# GSRv2.net
KiCad netlist of a schematic drawn in EAGLE
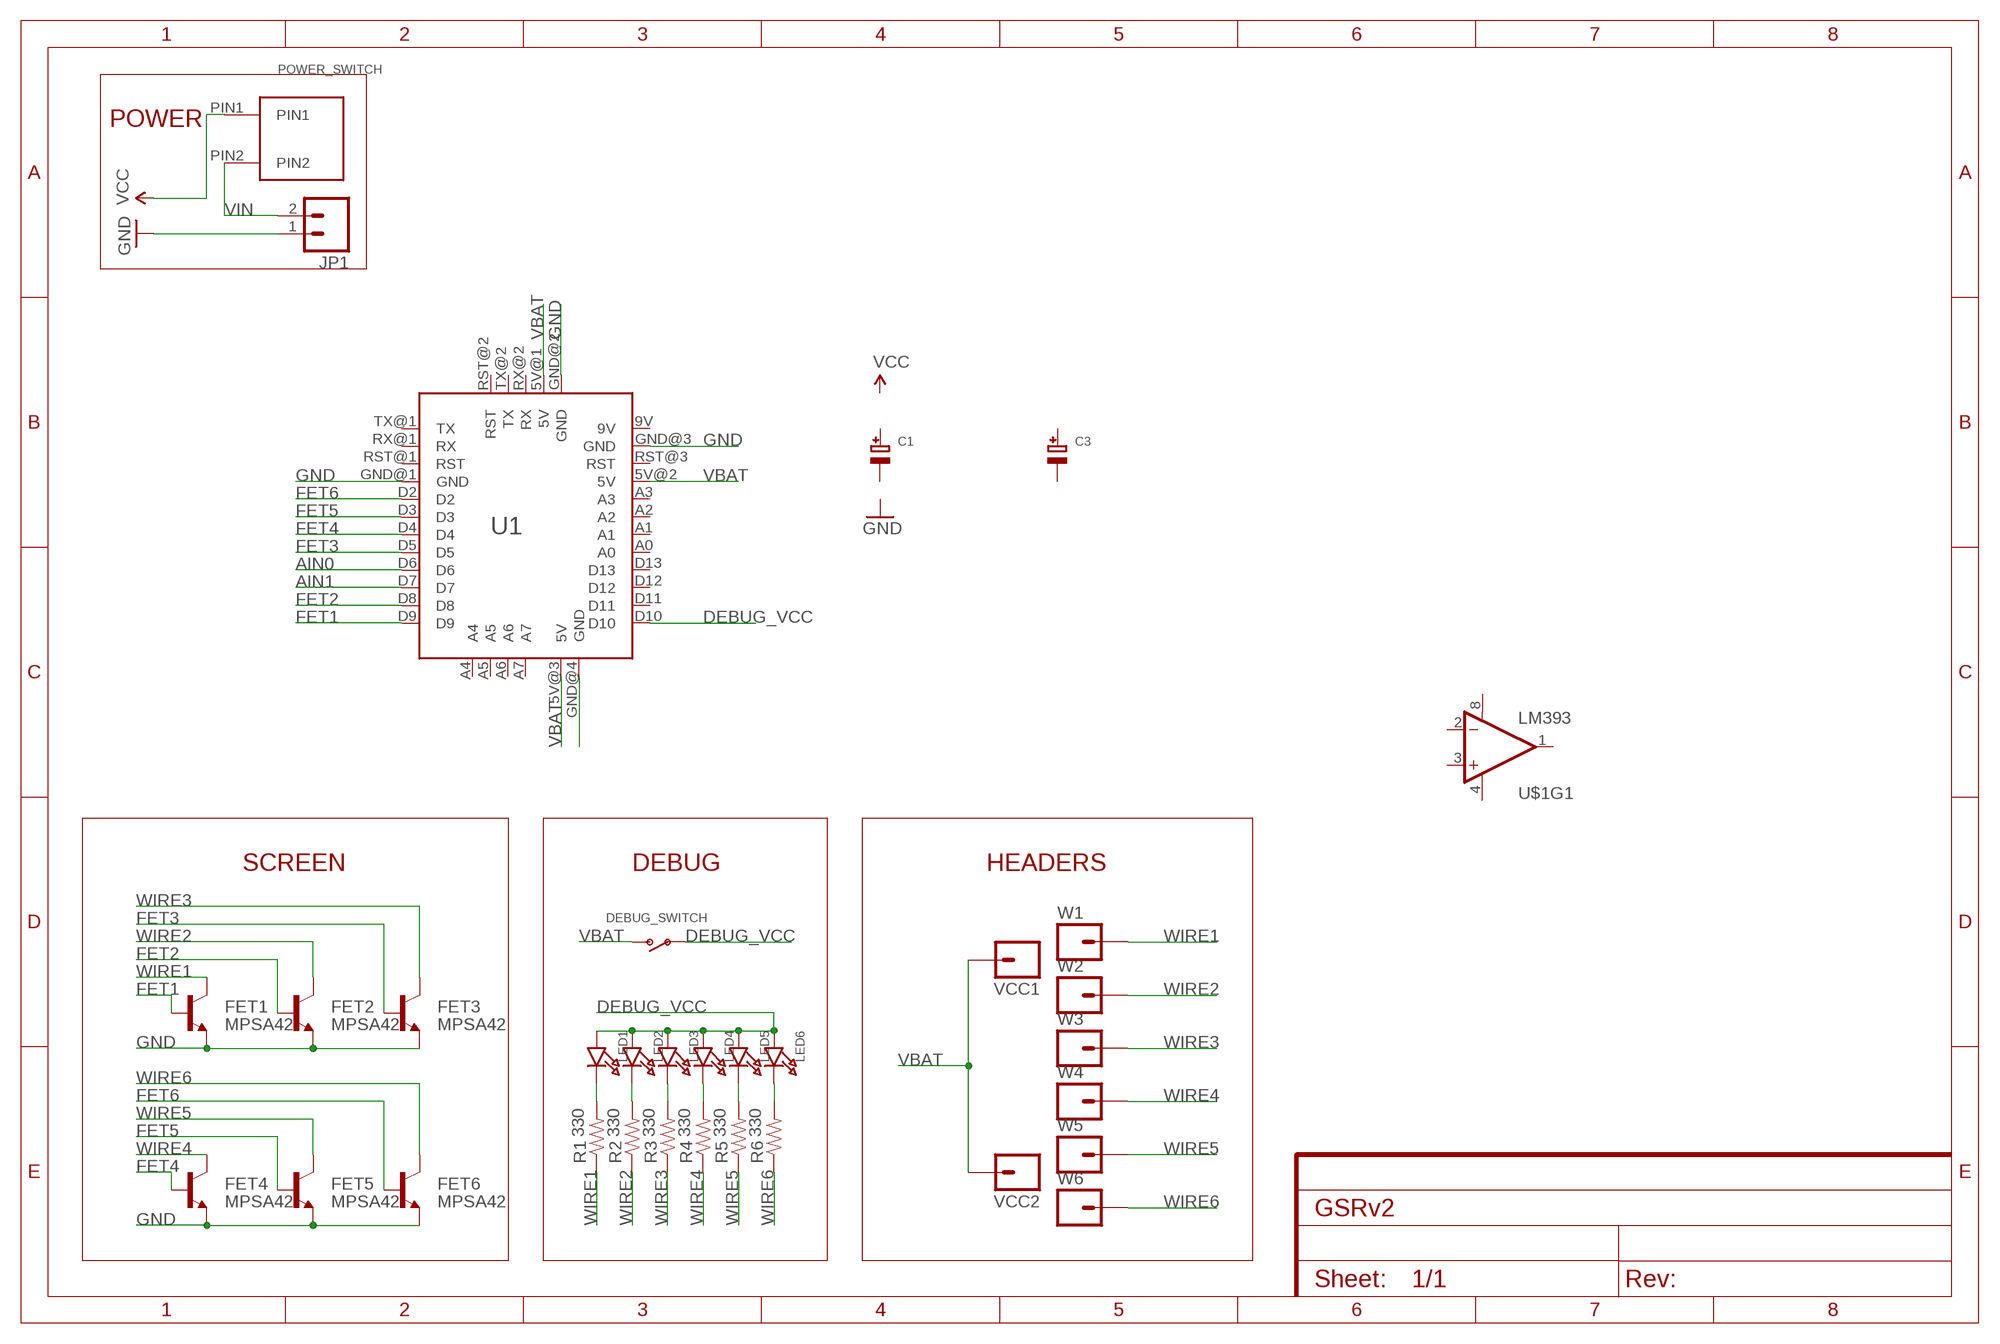
[diagram p0: schematic, sheet 1]

(export (version "E")
  (design (tool "Eeschema 10.0.6"))
  (components
    (comp (ref "C1")
      (value "CAP_TANTALUMB/3528_WAVE")
      (footprint "eagle-import:EIA3528-21_B-W")
      (libsource (lib "eagle-import") (part "CAP_TANTALUMB/3528_WAVE"))
    )
    (comp (ref "C3")
      (value "CAP_TANTALUMB/3528_WAVE")
      (footprint "eagle-import:EIA3528-21_B-W")
      (libsource (lib "eagle-import") (part "CAP_TANTALUMB/3528_WAVE"))
    )
    (comp (ref "DEBUG_SWITCH")
      (value "SWITCH_SPST")
      (footprint "eagle-import:SPST_SMT_19192")
      (libsource (lib "eagle-import") (part "SWITCH_SPST"))
    )
    (comp (ref "FET1")
      (value "MPSA42")
      (footprint "eagle-import:SOT23-3")
      (libsource (lib "eagle-import") (part "TRANSISTOR_NPNMPSA42"))
    )
    (comp (ref "FET2")
      (value "MPSA42")
      (footprint "eagle-import:SOT23-3")
      (libsource (lib "eagle-import") (part "TRANSISTOR_NPNMPSA42"))
    )
    (comp (ref "FET3")
      (value "MPSA42")
      (footprint "eagle-import:SOT23-3")
      (libsource (lib "eagle-import") (part "TRANSISTOR_NPNMPSA42"))
    )
    (comp (ref "FET4")
      (value "MPSA42")
      (footprint "eagle-import:SOT23-3")
      (libsource (lib "eagle-import") (part "TRANSISTOR_NPNMPSA42"))
    )
    (comp (ref "FET5")
      (value "MPSA42")
      (footprint "eagle-import:SOT23-3")
      (libsource (lib "eagle-import") (part "TRANSISTOR_NPNMPSA42"))
    )
    (comp (ref "FET6")
      (value "MPSA42")
      (footprint "eagle-import:SOT23-3")
      (libsource (lib "eagle-import") (part "TRANSISTOR_NPNMPSA42"))
    )
    (comp (ref "JP1")
      (value "M02-JST-2MM-SMT")
      (footprint "eagle-import:JST-2-SMD")
      (libsource (lib "eagle-import") (part "M02-JST-2MM-SMT"))
    )
    (comp (ref "LED1")
      (value "LED0603_NOOUTLINE")
      (footprint "eagle-import:CHIPLED_0603_NOOUTLINE")
      (libsource (lib "eagle-import") (part "LED0603_NOOUTLINE"))
    )
    (comp (ref "LED2")
      (value "LED0603_NOOUTLINE")
      (footprint "eagle-import:CHIPLED_0603_NOOUTLINE")
      (libsource (lib "eagle-import") (part "LED0603_NOOUTLINE"))
    )
    (comp (ref "LED3")
      (value "LED0603_NOOUTLINE")
      (footprint "eagle-import:CHIPLED_0603_NOOUTLINE")
      (libsource (lib "eagle-import") (part "LED0603_NOOUTLINE"))
    )
    (comp (ref "LED4")
      (value "LED0603_NOOUTLINE")
      (footprint "eagle-import:CHIPLED_0603_NOOUTLINE")
      (libsource (lib "eagle-import") (part "LED0603_NOOUTLINE"))
    )
    (comp (ref "LED5")
      (value "LED0603_NOOUTLINE")
      (footprint "eagle-import:CHIPLED_0603_NOOUTLINE")
      (libsource (lib "eagle-import") (part "LED0603_NOOUTLINE"))
    )
    (comp (ref "LED6")
      (value "LED0603_NOOUTLINE")
      (footprint "eagle-import:CHIPLED_0603_NOOUTLINE")
      (libsource (lib "eagle-import") (part "LED0603_NOOUTLINE"))
    )
    (comp (ref "POWER_SWITCH")
      (value "PUSH_BUTTON")
      (footprint "eagle-import:PUSH_BUTTON")
      (libsource (lib "eagle-import") (part "PUSH_BUTTON"))
    )
    (comp (ref "R1")
      (value "330")
      (footprint "eagle-import:0603-RES")
      (libsource (lib "eagle-import") (part "RESISTOR0603-RES"))
    )
    (comp (ref "R2")
      (value "330")
      (footprint "eagle-import:0603-RES")
      (libsource (lib "eagle-import") (part "RESISTOR0603-RES"))
    )
    (comp (ref "R3")
      (value "330")
      (footprint "eagle-import:0603-RES")
      (libsource (lib "eagle-import") (part "RESISTOR0603-RES"))
    )
    (comp (ref "R4")
      (value "330")
      (footprint "eagle-import:0603-RES")
      (libsource (lib "eagle-import") (part "RESISTOR0603-RES"))
    )
    (comp (ref "R5")
      (value "330")
      (footprint "eagle-import:0603-RES")
      (libsource (lib "eagle-import") (part "RESISTOR0603-RES"))
    )
    (comp (ref "R6")
      (value "330")
      (footprint "eagle-import:0603-RES")
      (libsource (lib "eagle-import") (part "RESISTOR0603-RES"))
    )
    (comp (ref "U$1")
      (value "LM393")
      (footprint "eagle-import:SO08")
      (libsource (lib "eagle-import") (part "LM393"))
    )
    (comp (ref "U1")
      (value "ARDUINO_MINI")
      (footprint "eagle-import:ARDUINO_MINI")
      (libsource (lib "eagle-import") (part "ARDUINO_MINI"))
    )
    (comp (ref "VCC1")
      (value "M01NOSILK-KIT")
      (footprint "eagle-import:1X01NS-KIT")
      (libsource (lib "eagle-import") (part "M01NOSILK-KIT"))
    )
    (comp (ref "VCC2")
      (value "M01NOSILK-KIT")
      (footprint "eagle-import:1X01NS-KIT")
      (libsource (lib "eagle-import") (part "M01NOSILK-KIT"))
    )
    (comp (ref "W1")
      (value "M01NOSILK-KIT")
      (footprint "eagle-import:1X01NS-KIT")
      (libsource (lib "eagle-import") (part "M01NOSILK-KIT"))
    )
    (comp (ref "W2")
      (value "M01NOSILK-KIT")
      (footprint "eagle-import:1X01NS-KIT")
      (libsource (lib "eagle-import") (part "M01NOSILK-KIT"))
    )
    (comp (ref "W3")
      (value "M01NOSILK-KIT")
      (footprint "eagle-import:1X01NS-KIT")
      (libsource (lib "eagle-import") (part "M01NOSILK-KIT"))
    )
    (comp (ref "W4")
      (value "M01NOSILK-KIT")
      (footprint "eagle-import:1X01NS-KIT")
      (libsource (lib "eagle-import") (part "M01NOSILK-KIT"))
    )
    (comp (ref "W5")
      (value "M01NOSILK-KIT")
      (footprint "eagle-import:1X01NS-KIT")
      (libsource (lib "eagle-import") (part "M01NOSILK-KIT"))
    )
    (comp (ref "W6")
      (value "M01NOSILK-KIT")
      (footprint "eagle-import:1X01NS-KIT")
      (libsource (lib "eagle-import") (part "M01NOSILK-KIT"))
    )
  )
  (nets
    (net (code "1") (name "/9V") (class "Default")
      (node (ref "U1") (pin "9V") (pinfunction "9V_9V") (pintype "power_in"))
    )
    (net (code "2") (name "/AIN0") (class "Default")
      (node (ref "U1") (pin "D6") (pinfunction "D6_D6") (pintype "bidirectional"))
    )
    (net (code "3") (name "/AIN1") (class "Default")
      (node (ref "U1") (pin "D7") (pinfunction "D7_D7") (pintype "bidirectional"))
    )
    (net (code "4") (name "/DEBUG_VCC") (class "Default")
      (node (ref "DEBUG_SWITCH") (pin "B") (pinfunction "P_B") (pintype "passive"))
      (node (ref "LED1") (pin "A") (pinfunction "A_A") (pintype "passive"))
      (node (ref "LED2") (pin "A") (pinfunction "A_A") (pintype "passive"))
      (node (ref "LED3") (pin "A") (pinfunction "A_A") (pintype "passive"))
      (node (ref "LED4") (pin "A") (pinfunction "A_A") (pintype "passive"))
      (node (ref "LED5") (pin "A") (pinfunction "A_A") (pintype "passive"))
      (node (ref "LED6") (pin "A") (pinfunction "A_A") (pintype "passive"))
      (node (ref "U1") (pin "D10") (pinfunction "D10_D10") (pintype "bidirectional"))
    )
    (net (code "5") (name "/FET1") (class "Default")
      (node (ref "FET1") (pin "1") (pinfunction "B_1") (pintype "passive"))
      (node (ref "U1") (pin "D9") (pinfunction "D9_D9") (pintype "bidirectional"))
    )
    (net (code "6") (name "/FET2") (class "Default")
      (node (ref "FET2") (pin "1") (pinfunction "B_1") (pintype "passive"))
      (node (ref "U1") (pin "D8") (pinfunction "D8_D8") (pintype "bidirectional"))
    )
    (net (code "7") (name "/FET3") (class "Default")
      (node (ref "FET3") (pin "1") (pinfunction "B_1") (pintype "passive"))
      (node (ref "U1") (pin "D5") (pinfunction "D5_D5") (pintype "bidirectional"))
    )
    (net (code "8") (name "/FET4") (class "Default")
      (node (ref "FET4") (pin "1") (pinfunction "B_1") (pintype "passive"))
      (node (ref "U1") (pin "D4") (pinfunction "D4_D4") (pintype "bidirectional"))
    )
    (net (code "9") (name "/FET5") (class "Default")
      (node (ref "FET5") (pin "1") (pinfunction "B_1") (pintype "passive"))
      (node (ref "U1") (pin "D3") (pinfunction "D3_D3") (pintype "bidirectional"))
    )
    (net (code "10") (name "/FET6") (class "Default")
      (node (ref "FET6") (pin "1") (pinfunction "B_1") (pintype "passive"))
      (node (ref "U1") (pin "D2") (pinfunction "D2_D2") (pintype "bidirectional"))
    )
    (net (code "11") (name "/V+") (class "Default")
      (node (ref "U$1") (pin "8") (pinfunction "V+_8") (pintype "power_in"))
    )
    (net (code "12") (name "/V-") (class "Default")
      (node (ref "U$1") (pin "4") (pinfunction "V-_4") (pintype "power_in"))
    )
    (net (code "13") (name "/VBAT") (class "Default")
      (node (ref "DEBUG_SWITCH") (pin "C") (pinfunction "S_C") (pintype "passive"))
      (node (ref "U1") (pin "5V@1") (pinfunction "5V_5V@1") (pintype "power_in"))
      (node (ref "U1") (pin "5V@2") (pinfunction "5V_5V@2") (pintype "power_in"))
      (node (ref "U1") (pin "5V@3") (pinfunction "5V_5V@3") (pintype "power_in"))
      (node (ref "VCC1") (pin "1") (pinfunction "1_1") (pintype "passive"))
      (node (ref "VCC2") (pin "1") (pinfunction "1_1") (pintype "passive"))
    )
    (net (code "14") (name "/VIN") (class "Default")
      (node (ref "JP1") (pin "2") (pinfunction "1_2") (pintype "passive"))
      (node (ref "POWER_SWITCH") (pin "PIN2") (pinfunction "PIN2_PIN2") (pintype "bidirectional"))
    )
    (net (code "15") (name "/WIRE1") (class "Default")
      (node (ref "FET1") (pin "3") (pinfunction "C_3") (pintype "passive"))
      (node (ref "R1") (pin "1") (pinfunction "1_1") (pintype "passive"))
      (node (ref "W1") (pin "1") (pinfunction "1_1") (pintype "passive"))
    )
    (net (code "16") (name "/WIRE2") (class "Default")
      (node (ref "FET2") (pin "3") (pinfunction "C_3") (pintype "passive"))
      (node (ref "R2") (pin "1") (pinfunction "1_1") (pintype "passive"))
      (node (ref "W2") (pin "1") (pinfunction "1_1") (pintype "passive"))
    )
    (net (code "17") (name "/WIRE3") (class "Default")
      (node (ref "FET3") (pin "3") (pinfunction "C_3") (pintype "passive"))
      (node (ref "R3") (pin "1") (pinfunction "1_1") (pintype "passive"))
      (node (ref "W3") (pin "1") (pinfunction "1_1") (pintype "passive"))
    )
    (net (code "18") (name "/WIRE4") (class "Default")
      (node (ref "FET4") (pin "3") (pinfunction "C_3") (pintype "passive"))
      (node (ref "R4") (pin "1") (pinfunction "1_1") (pintype "passive"))
      (node (ref "W4") (pin "1") (pinfunction "1_1") (pintype "passive"))
    )
    (net (code "19") (name "/WIRE5") (class "Default")
      (node (ref "FET5") (pin "3") (pinfunction "C_3") (pintype "passive"))
      (node (ref "R5") (pin "1") (pinfunction "1_1") (pintype "passive"))
      (node (ref "W5") (pin "1") (pinfunction "1_1") (pintype "passive"))
    )
    (net (code "20") (name "/WIRE6") (class "Default")
      (node (ref "FET6") (pin "3") (pinfunction "C_3") (pintype "passive"))
      (node (ref "R6") (pin "1") (pinfunction "1_1") (pintype "passive"))
      (node (ref "W6") (pin "1") (pinfunction "1_1") (pintype "passive"))
    )
    (net (code "21") (name "GND") (class "Default")
      (node (ref "FET1") (pin "2") (pinfunction "E_2") (pintype "passive"))
      (node (ref "FET2") (pin "2") (pinfunction "E_2") (pintype "passive"))
      (node (ref "FET3") (pin "2") (pinfunction "E_2") (pintype "passive"))
      (node (ref "FET4") (pin "2") (pinfunction "E_2") (pintype "passive"))
      (node (ref "FET5") (pin "2") (pinfunction "E_2") (pintype "passive"))
      (node (ref "FET6") (pin "2") (pinfunction "E_2") (pintype "passive"))
      (node (ref "JP1") (pin "1") (pinfunction "2_1") (pintype "passive"))
      (node (ref "U1") (pin "GND@1") (pinfunction "GND_GND@1") (pintype "power_in"))
      (node (ref "U1") (pin "GND@2") (pinfunction "GND_GND@2") (pintype "power_in"))
      (node (ref "U1") (pin "GND@3") (pinfunction "GND_GND@3") (pintype "power_in"))
      (node (ref "U1") (pin "GND@4") (pinfunction "GND_GND@4") (pintype "power_in"))
    )
    (net (code "22") (name "Net-(LED1-PadC)") (class "Default")
      (node (ref "LED1") (pin "C") (pinfunction "C_C") (pintype "passive"))
      (node (ref "R1") (pin "2") (pinfunction "2_2") (pintype "passive"))
    )
    (net (code "23") (name "Net-(LED2-PadC)") (class "Default")
      (node (ref "LED2") (pin "C") (pinfunction "C_C") (pintype "passive"))
      (node (ref "R2") (pin "2") (pinfunction "2_2") (pintype "passive"))
    )
    (net (code "24") (name "Net-(LED3-PadC)") (class "Default")
      (node (ref "LED3") (pin "C") (pinfunction "C_C") (pintype "passive"))
      (node (ref "R3") (pin "2") (pinfunction "2_2") (pintype "passive"))
    )
    (net (code "25") (name "Net-(LED4-PadC)") (class "Default")
      (node (ref "LED4") (pin "C") (pinfunction "C_C") (pintype "passive"))
      (node (ref "R4") (pin "2") (pinfunction "2_2") (pintype "passive"))
    )
    (net (code "26") (name "Net-(LED5-PadC)") (class "Default")
      (node (ref "LED5") (pin "C") (pinfunction "C_C") (pintype "passive"))
      (node (ref "R5") (pin "2") (pinfunction "2_2") (pintype "passive"))
    )
    (net (code "27") (name "Net-(LED6-PadC)") (class "Default")
      (node (ref "LED6") (pin "C") (pinfunction "C_C") (pintype "passive"))
      (node (ref "R6") (pin "2") (pinfunction "2_2") (pintype "passive"))
    )
    (net (code "28") (name "VCC") (class "Default")
      (node (ref "POWER_SWITCH") (pin "PIN1") (pinfunction "PIN1_PIN1") (pintype "bidirectional"))
    )
    (net (code "29") (name "unconnected-(C1-Pad+)") (class "Default")
      (node (ref "C1") (pin "+") (pinfunction "+_+") (pintype "passive"))
    )
    (net (code "30") (name "unconnected-(C1-Pad-)") (class "Default")
      (node (ref "C1") (pin "-") (pinfunction "-_-") (pintype "passive"))
    )
    (net (code "31") (name "unconnected-(C3-Pad+)") (class "Default")
      (node (ref "C3") (pin "+") (pinfunction "+_+") (pintype "passive"))
    )
    (net (code "32") (name "unconnected-(C3-Pad-)") (class "Default")
      (node (ref "C3") (pin "-") (pinfunction "-_-") (pintype "passive"))
    )
    (net (code "33") (name "unconnected-(U$1A-+IN-Pad3)") (class "Default")
      (node (ref "U$1") (pin "3") (pinfunction "+IN_3") (pintype "input"))
    )
    (net (code "34") (name "unconnected-(U$1A--IN-Pad2)") (class "Default")
      (node (ref "U$1") (pin "2") (pinfunction "-IN_2") (pintype "input"))
    )
    (net (code "35") (name "unconnected-(U$1A-OUT-Pad1)") (class "Default")
      (node (ref "U$1") (pin "1") (pinfunction "OUT_1") (pintype "output"))
    )
    (net (code "36") (name "unconnected-(U1-PadA0)") (class "Default")
      (node (ref "U1") (pin "A0") (pinfunction "A0_A0") (pintype "bidirectional"))
    )
    (net (code "37") (name "unconnected-(U1-PadA1)") (class "Default")
      (node (ref "U1") (pin "A1") (pinfunction "A1_A1") (pintype "bidirectional"))
    )
    (net (code "38") (name "unconnected-(U1-PadA2)") (class "Default")
      (node (ref "U1") (pin "A2") (pinfunction "A2_A2") (pintype "bidirectional"))
    )
    (net (code "39") (name "unconnected-(U1-PadA3)") (class "Default")
      (node (ref "U1") (pin "A3") (pinfunction "A3_A3") (pintype "bidirectional"))
    )
    (net (code "40") (name "unconnected-(U1-PadA4)") (class "Default")
      (node (ref "U1") (pin "A4") (pinfunction "A4_A4") (pintype "bidirectional"))
    )
    (net (code "41") (name "unconnected-(U1-PadA5)") (class "Default")
      (node (ref "U1") (pin "A5") (pinfunction "A5_A5") (pintype "bidirectional"))
    )
    (net (code "42") (name "unconnected-(U1-PadA6)") (class "Default")
      (node (ref "U1") (pin "A6") (pinfunction "A6_A6") (pintype "bidirectional"))
    )
    (net (code "43") (name "unconnected-(U1-PadA7)") (class "Default")
      (node (ref "U1") (pin "A7") (pinfunction "A7_A7") (pintype "bidirectional"))
    )
    (net (code "44") (name "unconnected-(U1-PadD11)") (class "Default")
      (node (ref "U1") (pin "D11") (pinfunction "D11_D11") (pintype "bidirectional"))
    )
    (net (code "45") (name "unconnected-(U1-PadD12)") (class "Default")
      (node (ref "U1") (pin "D12") (pinfunction "D12_D12") (pintype "bidirectional"))
    )
    (net (code "46") (name "unconnected-(U1-PadD13)") (class "Default")
      (node (ref "U1") (pin "D13") (pinfunction "D13_D13") (pintype "bidirectional"))
    )
    (net (code "47") (name "unconnected-(U1-RST-PadRST@1)") (class "Default")
      (node (ref "U1") (pin "RST@1") (pinfunction "RST_RST@1") (pintype "bidirectional"))
    )
    (net (code "48") (name "unconnected-(U1-RST-PadRST@2)") (class "Default")
      (node (ref "U1") (pin "RST@2") (pinfunction "RST_RST@2") (pintype "bidirectional"))
    )
    (net (code "49") (name "unconnected-(U1-RST-PadRST@3)") (class "Default")
      (node (ref "U1") (pin "RST@3") (pinfunction "RST_RST@3") (pintype "bidirectional"))
    )
    (net (code "50") (name "unconnected-(U1-RX-PadRX@1)") (class "Default")
      (node (ref "U1") (pin "RX@1") (pinfunction "RX_RX@1") (pintype "bidirectional"))
    )
    (net (code "51") (name "unconnected-(U1-RX-PadRX@2)") (class "Default")
      (node (ref "U1") (pin "RX@2") (pinfunction "RX_RX@2") (pintype "bidirectional"))
    )
    (net (code "52") (name "unconnected-(U1-TX-PadTX@1)") (class "Default")
      (node (ref "U1") (pin "TX@1") (pinfunction "TX_TX@1") (pintype "bidirectional"))
    )
    (net (code "53") (name "unconnected-(U1-TX-PadTX@2)") (class "Default")
      (node (ref "U1") (pin "TX@2") (pinfunction "TX_TX@2") (pintype "bidirectional"))
    )
  )
)
